# joint_board.net
KiCad netlist of a schematic drawn in Altium Designer
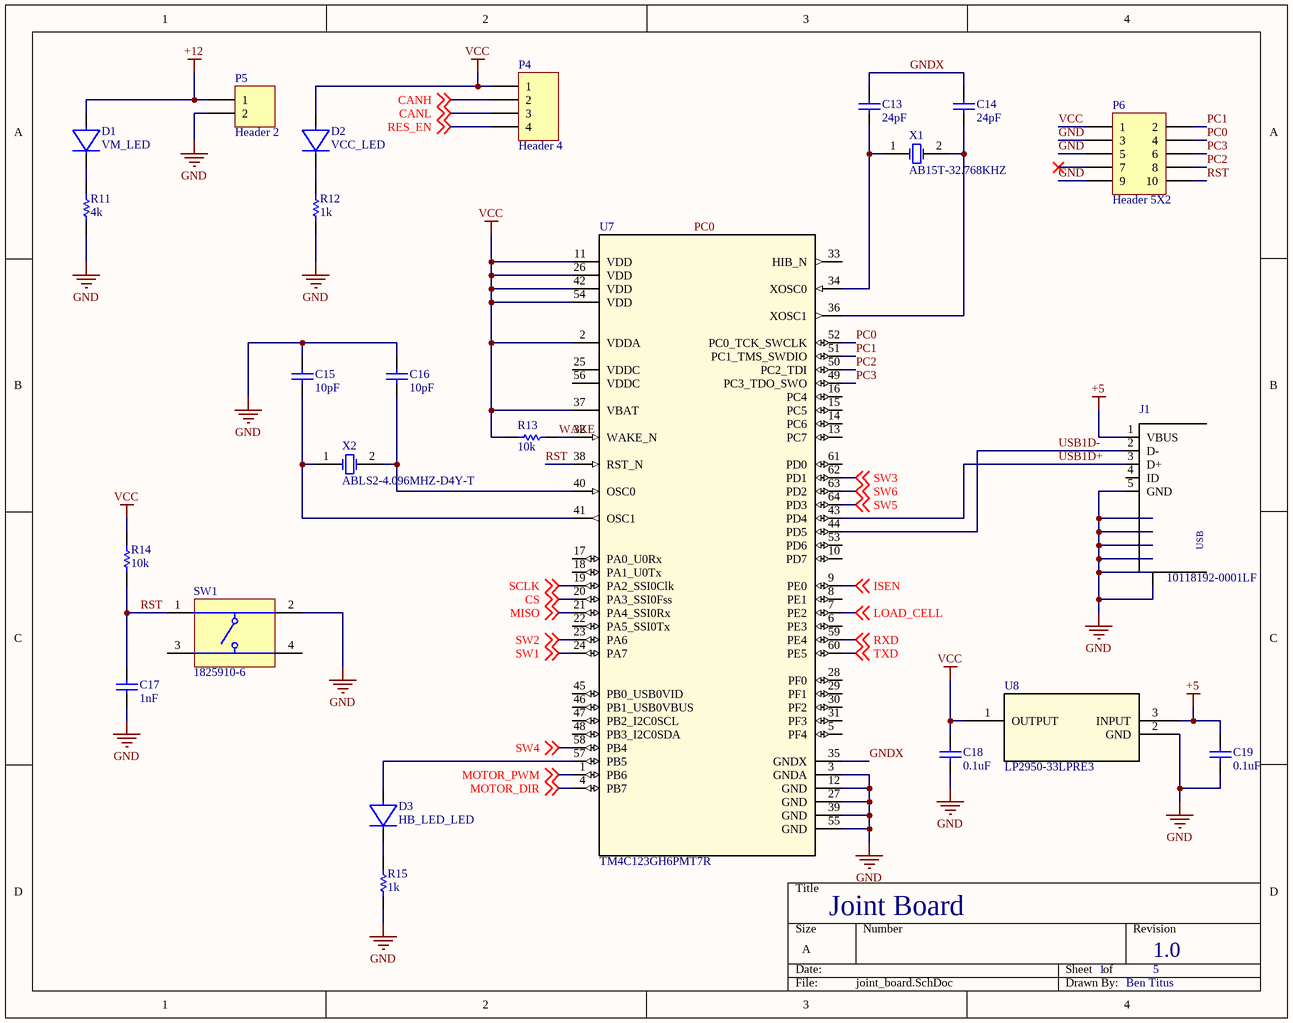
[diagram p0: joint_board.SchDoc]

(export (version "E")
  (design (tool "Eeschema 10.0.6"))
  (components
    (comp (ref "C13")
      (value "24pF")
      (footprint "CAPC0805(2012)145_L")
      (description "0805 (2012 Metric) Chip Capacitor")
      (libsource (lib "Altium Content Vault") (part "CAP_5"))
    )
    (comp (ref "C14")
      (value "24pF")
      (footprint "CAPC0805(2012)145_L")
      (description "0805 (2012 Metric) Chip Capacitor")
      (libsource (lib "Altium Content Vault") (part "CAP_5"))
    )
    (comp (ref "C15")
      (value "10pF")
      (footprint "CAPC0805(2012)145_L")
      (description "0805 (2012 Metric) Chip Capacitor")
      (libsource (lib "Altium Content Vault") (part "CAP_5"))
    )
    (comp (ref "C16")
      (value "10pF")
      (footprint "CAPC0805(2012)145_L")
      (description "0805 (2012 Metric) Chip Capacitor")
      (libsource (lib "Altium Content Vault") (part "CAP_5"))
    )
    (comp (ref "C17")
      (value "1nF")
      (footprint "CAPC0805(2012)145_L")
      (description "0805 (2012 Metric) Chip Capacitor")
      (libsource (lib "Altium Content Vault") (part "CAP_5"))
    )
    (comp (ref "C18")
      (value "0.1uF")
      (footprint "CAPC0805(2012)145_L")
      (description "0805 (2012 Metric) Chip Capacitor")
      (libsource (lib "Altium Content Vault") (part "CAP_5"))
    )
    (comp (ref "C19")
      (value "0.1uF")
      (footprint "CAPC0805(2012)145_L")
      (description "0805 (2012 Metric) Chip Capacitor")
      (libsource (lib "Altium Content Vault") (part "CAP_5"))
    )
    (comp (ref "D1")
      (value "VM_LED")
      (footprint "0805 Diode")
      (libsource (lib "Custom_Lib") (part "SMD_LED"))
    )
    (comp (ref "D2")
      (value "VCC_LED")
      (footprint "0805 Diode")
      (libsource (lib "Custom_Lib") (part "SMD_LED"))
    )
    (comp (ref "D3")
      (value "HB_LED_LED")
      (footprint "0805 Diode")
      (libsource (lib "Custom_Lib") (part "SMD_LED"))
    )
    (comp (ref "J1")
      (value "10118192-0001LF")
      (footprint "10118192-0001LF_10118192-0001LF(Primary)")
      (description "CONN USB MICRO B RECPT SMT R/A")
      (fields (field (name "MF") "Amphenol"))
      (libsource (lib "Custom_Lib") (part "10118192-0001LF"))
    )
    (comp (ref "P4")
      (value "Header 4")
      (footprint "HDR1X4")
      (description "Header, 4-Pin")
      (fields (field (name "PUBLISHER") "Altium Limited"))
      (libsource (lib "Miscellaneous Connectors") (part "Header 4"))
    )
    (comp (ref "P5")
      (value "Header 2")
      (footprint "HDR1X2")
      (description "Header, 2-Pin")
      (fields (field (name "PUBLISHER") "Altium Limited"))
      (libsource (lib "Miscellaneous Connectors") (part "Header 2"))
    )
    (comp (ref "P6")
      (value "Header 5X2")
      (footprint "HDR2X5")
      (description "Header, 5-Pin, Dual row")
      (fields (field (name "PUBLISHER") "Altium Limited"))
      (libsource (lib "Miscellaneous Connectors") (part "Header 5X2"))
    )
    (comp (ref "R11")
      (value "4k")
      (footprint "RESC0805(2012)_L")
      (description "0805 (2012 Metric) Chip Resistor")
      (libsource (lib "Altium Content Vault") (part "RES_3"))
    )
    (comp (ref "R12")
      (value "1k")
      (footprint "RESC0805(2012)_L")
      (description "0805 (2012 Metric) Chip Resistor")
      (libsource (lib "Altium Content Vault") (part "RES_3"))
    )
    (comp (ref "R13")
      (value "10k")
      (footprint "RESC0805(2012)_L")
      (description "0805 (2012 Metric) Chip Resistor")
      (libsource (lib "Altium Content Vault") (part "RES_3"))
    )
    (comp (ref "R14")
      (value "10k")
      (footprint "RESC0805(2012)_L")
      (description "0805 (2012 Metric) Chip Resistor")
      (libsource (lib "Altium Content Vault") (part "RES_3"))
    )
    (comp (ref "R15")
      (value "1k")
      (footprint "RESC0805(2012)_L")
      (description "0805 (2012 Metric) Chip Resistor")
      (libsource (lib "Altium Content Vault") (part "RES_3"))
    )
    (comp (ref "SW1")
      (value "1825910-6")
      (footprint "TECO-1825910-6_V")
      (description "Tact Switch, SPST-NO, 0.05 A, -35 to 85 degC, 4-Pin THD, RoHS, Bulk")
      (fields (field (name "MANUFACTURER") "TE Connectivity"))
      (libsource (lib "Altium Content Vault") (part "SW-SPST-4_A"))
    )
    (comp (ref "U7")
      (value "TM4C123GH6PMT7R")
      (footprint "PM0064A_N")
      (description "Imported")
      (fields
        (field (name "PARTNUMBER") "TM4C123GH6PMTR")
        (field (name "ALTERNATE_PARTNUMBER") "TM4C123GH6PMT")
      )
      (libsource (lib "Custom_Lib") (part "TM4C123GH6PMT7R"))
    )
    (comp (ref "U8")
      (value "LP2950-33LPRE3")
      (footprint "LP3")
      (description "Imported")
      (fields (field (name "MANUFACTURER") "Texas Instruments"))
      (libsource (lib "lp2950-33") (part "LP2950-33LPRE3"))
    )
    (comp (ref "X1")
      (value "AB15T-32.768KHZ")
      (footprint "ABRA-AB15T-2_V")
      (fields (field (name "MANUFACTURER") "Abracon"))
      (libsource (lib "Altium Content Vault") (part "ABRA-XTAL_1-2-2"))
    )
    (comp (ref "X2")
      (value "ABLS2-4.096MHZ-D4Y-T")
      (footprint "ABRA-ABLS2-2_V")
      (fields (field (name "MANUFACTURER") "Abracon"))
      (libsource (lib "Altium Content Vault") (part "ABRA-XTAL_1-2-2"))
    )
  )
  (nets
    (net (code "1") (name "+5") (class "Default")
      (node (ref "C19") (pin "2") (pinfunction "2_2") (pintype "passive"))
      (node (ref "J1") (pin "1") (pinfunction "VBUS_1") (pintype "passive"))
      (node (ref "U8") (pin "3") (pinfunction "INPUT_3") (pintype "power_in"))
    )
    (net (code "2") (name "+12") (class "Default")
      (node (ref "D1") (pin "1") (pintype "passive"))
      (node (ref "P5") (pin "1") (pinfunction "1_1") (pintype "passive"))
    )
    (net (code "3") (name "/GNDX") (class "Default")
      (node (ref "C13") (pin "2") (pinfunction "2_2") (pintype "passive"))
      (node (ref "C14") (pin "2") (pinfunction "2_2") (pintype "passive"))
      (node (ref "U7") (pin "35") (pinfunction "GNDX_35") (pintype "power_in"))
    )
    (net (code "4") (name "/PC0") (class "Default")
      (node (ref "P6") (pin "4") (pinfunction "4_4") (pintype "passive"))
      (node (ref "U7") (pin "52") (pinfunction "PC0_TCK_SWCLK_52") (pintype "bidirectional"))
    )
    (net (code "5") (name "/PC1") (class "Default")
      (node (ref "P6") (pin "2") (pinfunction "2_2") (pintype "passive"))
      (node (ref "U7") (pin "51") (pinfunction "PC1_TMS_SWDIO_51") (pintype "bidirectional"))
    )
    (net (code "6") (name "/PC2") (class "Default")
      (node (ref "P6") (pin "8") (pinfunction "8_8") (pintype "passive"))
      (node (ref "U7") (pin "50") (pinfunction "PC2_TDI_50") (pintype "bidirectional"))
    )
    (net (code "7") (name "/PC3") (class "Default")
      (node (ref "P6") (pin "6") (pinfunction "6_6") (pintype "passive"))
      (node (ref "U7") (pin "49") (pinfunction "PC3_TDO_SWO_49") (pintype "bidirectional"))
    )
    (net (code "8") (name "/RST") (class "Default")
      (node (ref "C17") (pin "2") (pinfunction "2_2") (pintype "passive"))
      (node (ref "P6") (pin "10") (pinfunction "10_10") (pintype "passive"))
      (node (ref "R14") (pin "1") (pinfunction "1_1") (pintype "passive"))
      (node (ref "SW1") (pin "1") (pinfunction "1_1") (pintype "passive"))
      (node (ref "U7") (pin "38") (pinfunction "RST_N_38") (pintype "input"))
    )
    (net (code "9") (name "/USB1D+") (class "Default")
      (node (ref "J1") (pin "3") (pinfunction "D+_3") (pintype "passive"))
      (node (ref "U7") (pin "43") (pinfunction "PD4_43") (pintype "bidirectional"))
    )
    (net (code "10") (name "/USB1D-") (class "Default")
      (node (ref "J1") (pin "2") (pinfunction "D-_2") (pintype "passive"))
      (node (ref "U7") (pin "44") (pinfunction "PD5_44") (pintype "bidirectional"))
    )
    (net (code "11") (name "/WAKE") (class "Default")
      (node (ref "R13") (pin "2") (pinfunction "2_2") (pintype "passive"))
      (node (ref "U7") (pin "32") (pinfunction "WAKE_N_32") (pintype "input"))
    )
    (net (code "12") (name "CANH") (class "Default")
      (node (ref "P4") (pin "2") (pinfunction "2_2") (pintype "passive"))
    )
    (net (code "13") (name "CANL") (class "Default")
      (node (ref "P4") (pin "3") (pinfunction "3_3") (pintype "passive"))
    )
    (net (code "14") (name "CS") (class "Default")
      (node (ref "U7") (pin "20") (pinfunction "PA3_SSI0Fss_20") (pintype "bidirectional"))
    )
    (net (code "15") (name "GND") (class "Default")
      (node (ref "C15") (pin "2") (pinfunction "2_2") (pintype "passive"))
      (node (ref "C16") (pin "2") (pinfunction "2_2") (pintype "passive"))
      (node (ref "C17") (pin "1") (pinfunction "1_1") (pintype "passive"))
      (node (ref "C18") (pin "1") (pinfunction "1_1") (pintype "passive"))
      (node (ref "C19") (pin "1") (pinfunction "1_1") (pintype "passive"))
      (node (ref "J1") (pin "5") (pinfunction "GND_5") (pintype "passive"))
      (node (ref "J1") (pin "M1") (pinfunction "S_M1") (pintype "passive"))
      (node (ref "J1") (pin "M2") (pinfunction "S_M2") (pintype "passive"))
      (node (ref "J1") (pin "S1") (pinfunction "S_S1") (pintype "passive"))
      (node (ref "J1") (pin "S2") (pinfunction "S_S2") (pintype "passive"))
      (node (ref "J1") (pin "S3") (pinfunction "S_S3") (pintype "passive"))
      (node (ref "J1") (pin "S4") (pinfunction "S_S4") (pintype "passive"))
      (node (ref "P5") (pin "2") (pinfunction "2_2") (pintype "passive"))
      (node (ref "P6") (pin "3") (pinfunction "3_3") (pintype "passive"))
      (node (ref "P6") (pin "5") (pinfunction "5_5") (pintype "passive"))
      (node (ref "P6") (pin "9") (pinfunction "9_9") (pintype "passive"))
      (node (ref "R11") (pin "1") (pinfunction "1_1") (pintype "passive"))
      (node (ref "R12") (pin "1") (pinfunction "1_1") (pintype "passive"))
      (node (ref "R15") (pin "1") (pinfunction "1_1") (pintype "passive"))
      (node (ref "SW1") (pin "2") (pinfunction "2_2") (pintype "passive"))
      (node (ref "U7") (pin "12") (pinfunction "GND_12") (pintype "power_in"))
      (node (ref "U7") (pin "27") (pinfunction "GND_27") (pintype "power_in"))
      (node (ref "U7") (pin "3") (pinfunction "GNDA_3") (pintype "power_in"))
      (node (ref "U7") (pin "39") (pinfunction "GND_39") (pintype "power_in"))
      (node (ref "U7") (pin "55") (pinfunction "GND_55") (pintype "power_in"))
      (node (ref "U8") (pin "2") (pinfunction "GND_2") (pintype "power_in"))
    )
    (net (code "16") (name "ISEN") (class "Default")
      (node (ref "U7") (pin "9") (pinfunction "PE0_9") (pintype "bidirectional"))
    )
    (net (code "17") (name "LOAD_CELL") (class "Default")
      (node (ref "U7") (pin "7") (pinfunction "PE2_7") (pintype "bidirectional"))
    )
    (net (code "18") (name "MISO") (class "Default")
      (node (ref "U7") (pin "21") (pinfunction "PA4_SSI0Rx_21") (pintype "bidirectional"))
    )
    (net (code "19") (name "MOTOR_DIR") (class "Default")
      (node (ref "U7") (pin "4") (pinfunction "PB7_4") (pintype "bidirectional"))
    )
    (net (code "20") (name "MOTOR_PWM") (class "Default")
      (node (ref "U7") (pin "1") (pinfunction "PB6_1") (pintype "bidirectional"))
    )
    (net (code "21") (name "Net-(D1-Pad2)") (class "Default")
      (node (ref "D1") (pin "2") (pintype "passive"))
      (node (ref "R11") (pin "2") (pinfunction "2_2") (pintype "passive"))
    )
    (net (code "22") (name "Net-(D2-Pad2)") (class "Default")
      (node (ref "D2") (pin "2") (pintype "passive"))
      (node (ref "R12") (pin "2") (pinfunction "2_2") (pintype "passive"))
    )
    (net (code "23") (name "Net-(D3-Pad2)") (class "Default")
      (node (ref "D3") (pin "2") (pintype "passive"))
      (node (ref "R15") (pin "2") (pinfunction "2_2") (pintype "passive"))
    )
    (net (code "24") (name "Net-(U7-OSC0)") (class "Default")
      (node (ref "C16") (pin "1") (pinfunction "1_1") (pintype "passive"))
      (node (ref "U7") (pin "40") (pinfunction "OSC0_40") (pintype "input"))
      (node (ref "X2") (pin "2") (pinfunction "X2_2") (pintype "passive"))
    )
    (net (code "25") (name "Net-(U7-OSC1)") (class "Default")
      (node (ref "C15") (pin "1") (pinfunction "1_1") (pintype "passive"))
      (node (ref "U7") (pin "41") (pinfunction "OSC1_41") (pintype "output"))
      (node (ref "X2") (pin "1") (pinfunction "X1_1") (pintype "passive"))
    )
    (net (code "26") (name "Net-(U7-PB5)") (class "Default")
      (node (ref "D3") (pin "1") (pintype "passive"))
      (node (ref "U7") (pin "57") (pinfunction "PB5_57") (pintype "bidirectional"))
    )
    (net (code "27") (name "Net-(U7-XOSC0)") (class "Default")
      (node (ref "C13") (pin "1") (pinfunction "1_1") (pintype "passive"))
      (node (ref "U7") (pin "34") (pinfunction "XOSC0_34") (pintype "input"))
      (node (ref "X1") (pin "1") (pinfunction "X1_1") (pintype "passive"))
    )
    (net (code "28") (name "Net-(U7-XOSC1)") (class "Default")
      (node (ref "C14") (pin "1") (pinfunction "1_1") (pintype "passive"))
      (node (ref "U7") (pin "36") (pinfunction "XOSC1_36") (pintype "output"))
      (node (ref "X1") (pin "2") (pinfunction "X2_2") (pintype "passive"))
    )
    (net (code "29") (name "RES_EN") (class "Default")
      (node (ref "P4") (pin "4") (pinfunction "4_4") (pintype "passive"))
    )
    (net (code "30") (name "RXD") (class "Default")
      (node (ref "U7") (pin "59") (pinfunction "PE4_59") (pintype "bidirectional"))
    )
    (net (code "31") (name "SCLK") (class "Default")
      (node (ref "U7") (pin "19") (pinfunction "PA2_SSI0Clk_19") (pintype "bidirectional"))
    )
    (net (code "32") (name "SW1") (class "Default")
      (node (ref "U7") (pin "24") (pinfunction "PA7_24") (pintype "bidirectional"))
    )
    (net (code "33") (name "SW2") (class "Default")
      (node (ref "U7") (pin "23") (pinfunction "PA6_23") (pintype "bidirectional"))
    )
    (net (code "34") (name "SW3") (class "Default")
      (node (ref "U7") (pin "62") (pinfunction "PD1_62") (pintype "bidirectional"))
    )
    (net (code "35") (name "SW4") (class "Default")
      (node (ref "U7") (pin "58") (pinfunction "PB4_58") (pintype "bidirectional"))
    )
    (net (code "36") (name "SW5") (class "Default")
      (node (ref "U7") (pin "64") (pinfunction "PD3_64") (pintype "bidirectional"))
    )
    (net (code "37") (name "SW6") (class "Default")
      (node (ref "U7") (pin "63") (pinfunction "PD2_63") (pintype "bidirectional"))
    )
    (net (code "38") (name "TXD") (class "Default")
      (node (ref "U7") (pin "60") (pinfunction "PE5_60") (pintype "bidirectional"))
    )
    (net (code "39") (name "VCC") (class "Default")
      (node (ref "C18") (pin "2") (pinfunction "2_2") (pintype "passive"))
      (node (ref "D2") (pin "1") (pintype "passive"))
      (node (ref "P4") (pin "1") (pinfunction "1_1") (pintype "passive"))
      (node (ref "P6") (pin "1") (pinfunction "1_1") (pintype "passive"))
      (node (ref "R13") (pin "1") (pinfunction "1_1") (pintype "passive"))
      (node (ref "R14") (pin "2") (pinfunction "2_2") (pintype "passive"))
      (node (ref "U7") (pin "11") (pinfunction "VDD_11") (pintype "power_in"))
      (node (ref "U7") (pin "2") (pinfunction "VDDA_2") (pintype "power_in"))
      (node (ref "U7") (pin "26") (pinfunction "VDD_26") (pintype "power_in"))
      (node (ref "U7") (pin "37") (pinfunction "VBAT_37") (pintype "power_in"))
      (node (ref "U7") (pin "42") (pinfunction "VDD_42") (pintype "power_in"))
      (node (ref "U7") (pin "54") (pinfunction "VDD_54") (pintype "power_in"))
      (node (ref "U8") (pin "1") (pinfunction "OUTPUT_1") (pintype "power_in"))
    )
    (net (code "40") (name "unconnected-(J1-ID-Pad4)") (class "Default")
      (node (ref "J1") (pin "4") (pinfunction "ID_4") (pintype "passive"))
    )
    (net (code "41") (name "unconnected-(P6-Pad7)") (class "Default")
      (node (ref "P6") (pin "7") (pinfunction "7_7") (pintype "passive+no_connect"))
    )
    (net (code "42") (name "unconnected-(SW1-Pad3)") (class "Default")
      (node (ref "SW1") (pin "3") (pinfunction "3_3") (pintype "passive"))
    )
    (net (code "43") (name "unconnected-(SW1-Pad4)") (class "Default")
      (node (ref "SW1") (pin "4") (pinfunction "4_4") (pintype "passive"))
    )
    (net (code "44") (name "unconnected-(U7-HIB_N-Pad33)") (class "Default")
      (node (ref "U7") (pin "33") (pinfunction "HIB_N_33") (pintype "output"))
    )
    (net (code "45") (name "unconnected-(U7-PA0_U0Rx-Pad17)") (class "Default")
      (node (ref "U7") (pin "17") (pinfunction "PA0_U0Rx_17") (pintype "bidirectional"))
    )
    (net (code "46") (name "unconnected-(U7-PA1_U0Tx-Pad18)") (class "Default")
      (node (ref "U7") (pin "18") (pinfunction "PA1_U0Tx_18") (pintype "bidirectional"))
    )
    (net (code "47") (name "unconnected-(U7-PA5_SSI0Tx-Pad22)") (class "Default")
      (node (ref "U7") (pin "22") (pinfunction "PA5_SSI0Tx_22") (pintype "bidirectional"))
    )
    (net (code "48") (name "unconnected-(U7-PB0_USB0VID-Pad45)") (class "Default")
      (node (ref "U7") (pin "45") (pinfunction "PB0_USB0VID_45") (pintype "bidirectional"))
    )
    (net (code "49") (name "unconnected-(U7-PB1_USB0VBUS-Pad46)") (class "Default")
      (node (ref "U7") (pin "46") (pinfunction "PB1_USB0VBUS_46") (pintype "bidirectional"))
    )
    (net (code "50") (name "unconnected-(U7-PB2_I2C0SCL-Pad47)") (class "Default")
      (node (ref "U7") (pin "47") (pinfunction "PB2_I2C0SCL_47") (pintype "bidirectional"))
    )
    (net (code "51") (name "unconnected-(U7-PB3_I2C0SDA-Pad48)") (class "Default")
      (node (ref "U7") (pin "48") (pinfunction "PB3_I2C0SDA_48") (pintype "bidirectional"))
    )
    (net (code "52") (name "unconnected-(U7-PC4-Pad16)") (class "Default")
      (node (ref "U7") (pin "16") (pinfunction "PC4_16") (pintype "bidirectional"))
    )
    (net (code "53") (name "unconnected-(U7-PC5-Pad15)") (class "Default")
      (node (ref "U7") (pin "15") (pinfunction "PC5_15") (pintype "bidirectional"))
    )
    (net (code "54") (name "unconnected-(U7-PC6-Pad14)") (class "Default")
      (node (ref "U7") (pin "14") (pinfunction "PC6_14") (pintype "bidirectional"))
    )
    (net (code "55") (name "unconnected-(U7-PC7-Pad13)") (class "Default")
      (node (ref "U7") (pin "13") (pinfunction "PC7_13") (pintype "bidirectional"))
    )
    (net (code "56") (name "unconnected-(U7-PD0-Pad61)") (class "Default")
      (node (ref "U7") (pin "61") (pinfunction "PD0_61") (pintype "bidirectional"))
    )
    (net (code "57") (name "unconnected-(U7-PD6-Pad53)") (class "Default")
      (node (ref "U7") (pin "53") (pinfunction "PD6_53") (pintype "bidirectional"))
    )
    (net (code "58") (name "unconnected-(U7-PD7-Pad10)") (class "Default")
      (node (ref "U7") (pin "10") (pinfunction "PD7_10") (pintype "bidirectional"))
    )
    (net (code "59") (name "unconnected-(U7-PE1-Pad8)") (class "Default")
      (node (ref "U7") (pin "8") (pinfunction "PE1_8") (pintype "bidirectional"))
    )
    (net (code "60") (name "unconnected-(U7-PE3-Pad6)") (class "Default")
      (node (ref "U7") (pin "6") (pinfunction "PE3_6") (pintype "bidirectional"))
    )
    (net (code "61") (name "unconnected-(U7-PF0-Pad28)") (class "Default")
      (node (ref "U7") (pin "28") (pinfunction "PF0_28") (pintype "bidirectional"))
    )
    (net (code "62") (name "unconnected-(U7-PF1-Pad29)") (class "Default")
      (node (ref "U7") (pin "29") (pinfunction "PF1_29") (pintype "bidirectional"))
    )
    (net (code "63") (name "unconnected-(U7-PF2-Pad30)") (class "Default")
      (node (ref "U7") (pin "30") (pinfunction "PF2_30") (pintype "bidirectional"))
    )
    (net (code "64") (name "unconnected-(U7-PF3-Pad31)") (class "Default")
      (node (ref "U7") (pin "31") (pinfunction "PF3_31") (pintype "bidirectional"))
    )
    (net (code "65") (name "unconnected-(U7-PF4-Pad5)") (class "Default")
      (node (ref "U7") (pin "5") (pinfunction "PF4_5") (pintype "bidirectional"))
    )
    (net (code "66") (name "unconnected-(U7-VDDC-Pad25)") (class "Default")
      (node (ref "U7") (pin "25") (pinfunction "VDDC_25") (pintype "power_in"))
    )
    (net (code "67") (name "unconnected-(U7-VDDC-Pad56)") (class "Default")
      (node (ref "U7") (pin "56") (pinfunction "VDDC_56") (pintype "power_in"))
    )
  )
)
